# CC2538_Flashing_-_FTDI.net
KiCad netlist of a schematic drawn in Altium Designer
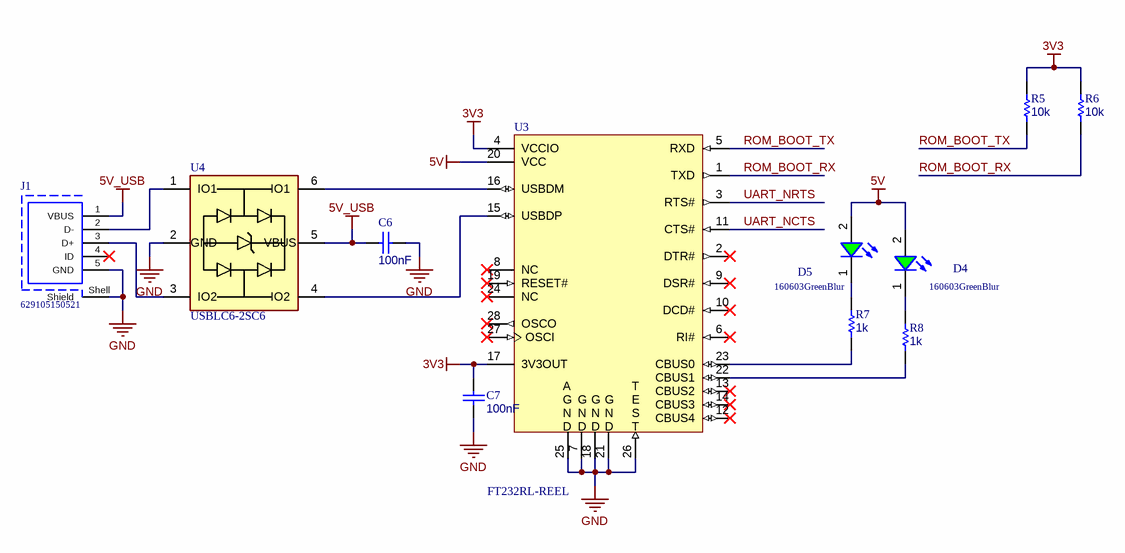
[diagram p0: [CC2538] Flashing - FTDI.SchDoc]

(export (version "E")
  (design (tool "Eeschema 10.0.6"))
  (components
    (comp (ref "C6")
      (value "100nF")
      (footprint "CAP_0603")
      (description "CAP, size 0603, 100 nF, 50 VDC, 10%")
      (fields
        (field (name "MANUFACTURER PART NUMBER") "CGA3E3X8R1H104K080AE")
        (field (name "LCSC PART #") "C14663")
        (field (name "SOURCE") "Capacitor_0603_10_percent.SchLib")
      )
      (libsource (lib "University of Technology") (part "010603475106.3"))
    )
    (comp (ref "C7")
      (value "100nF")
      (footprint "CAP_0603")
      (description "CAP, size 0603, 100 nF, 50 VDC, 10%")
      (fields
        (field (name "MANUFACTURER PART NUMBER") "CGA3E3X8R1H104K080AE")
        (field (name "LCSC PART #") "C14663")
        (field (name "SOURCE") "Capacitor_0603_10_percent.SchLib")
      )
      (libsource (lib "University of Technology") (part "010603475106.3"))
    )
    (comp (ref "D4")
      (value "160603GreenBlur")
      (footprint "WL-SMCW_0603_H=0.7mm")
      (description "WL-SMCW SMT Mono-color Chip LED Blur, size 0603, Green, 3.2V, 140deg")
      (libsource (lib "University of Technology") (part "160603GreenClear"))
    )
    (comp (ref "D5")
      (value "160603GreenBlur")
      (footprint "WL-SMCW_0603_H=0.7mm")
      (description "WL-SMCW SMT Mono-color Chip LED Blur, size 0603, Green, 3.2V, 140deg")
      (libsource (lib "University of Technology") (part "160603GreenClear"))
    )
    (comp (ref "J1")
      (value "629105150521")
      (footprint "629105150521")
      (description "Micro USB 2.0 Type B Receptacle WR-COM, Horizontal, SMT, with Pegs, High Current at Pin 1 & Pin 5")
      (libsource (lib "University of Technology") (part "Micro USB 2.0"))
    )
    (comp (ref "R5")
      (value "10k")
      (footprint "RES_0603")
      (description "RES, size 0603, 10 KOhm, 1/10 W, 1%")
      (fields
        (field (name "MANUFACTURER PART NUMBER") "RC0603FR-0710KL")
        (field (name "MANUFACTURER") "YAGEO")
      )
      (libsource (lib "University of Technology") (part "00060371541"))
    )
    (comp (ref "R6")
      (value "10k")
      (footprint "RES_0603")
      (description "RES, size 0603, 10 KOhm, 1/10 W, 1%")
      (fields
        (field (name "MANUFACTURER PART NUMBER") "RC0603FR-0710KL")
        (field (name "MANUFACTURER") "YAGEO")
      )
      (libsource (lib "University of Technology") (part "00060371541"))
    )
    (comp (ref "R7")
      (value "1k")
      (footprint "RES_0603")
      (description "RES, size 0603, 1 KOhm, 1/10 W, 1%")
      (fields (field (name "TOLERANCE") "1%") (field (name "MANUFACTURER PART NUMBER") "RC0603FR-071KL"))
      (libsource (lib "University of Technology") (part "00060371541"))
    )
    (comp (ref "R8")
      (value "1k")
      (footprint "RES_0603")
      (description "RES, size 0603, 1 KOhm, 1/10 W, 1%")
      (fields (field (name "TOLERANCE") "1%") (field (name "MANUFACTURER PART NUMBER") "RC0603FR-071KL"))
      (libsource (lib "University of Technology") (part "00060371541"))
    )
    (comp (ref "U3")
      (value "FT232RL-REEL")
      (footprint "FTDI-SSOP-28_L")
      (description "USB UART IC, -0.5 to 6 V, 24 mA, -40 to 85 degC, 28-Pin SSOP, RoHS, Tape and Reel")
      (fields (field (name "MANUFACTURER") "Future Technology Devices International (FTDI)"))
      (libsource (lib "University of Technology") (part "FTDI-FT232-SSOP-28"))
    )
    (comp (ref "U4")
      (value "USBLC6-2SC6")
      (footprint "USBLC6-2SC6-Footprint-1")
      (description "17V Clamp 5A (8/20Âµs) Ipp Tvs Diode Surface Mount SOT-23-6")
      (libsource (lib "University of Technology") (part "USBLC6"))
    )
  )
  (nets
    (net (code "1") (name "/ROM_BOOT_RX") (class "Default")
      (node (ref "R6") (pin "1") (pinfunction "1_1") (pintype "passive"))
      (node (ref "U3") (pin "1") (pinfunction "TXD_1") (pintype "output"))
    )
    (net (code "2") (name "/ROM_BOOT_TX") (class "Default")
      (node (ref "R5") (pin "1") (pinfunction "1_1") (pintype "passive"))
      (node (ref "U3") (pin "5") (pinfunction "RXD_5") (pintype "input"))
    )
    (net (code "3") (name "/UART_NCTS") (class "Default")
      (node (ref "U3") (pin "11") (pinfunction "CTS#_11") (pintype "input"))
    )
    (net (code "4") (name "/UART_NRTS") (class "Default")
      (node (ref "U3") (pin "3") (pinfunction "RTS#_3") (pintype "output"))
    )
    (net (code "5") (name "3V3") (class "Default")
      (node (ref "C7") (pin "2") (pinfunction "2_2") (pintype "passive"))
      (node (ref "R5") (pin "2") (pinfunction "2_2") (pintype "passive"))
      (node (ref "R6") (pin "2") (pinfunction "2_2") (pintype "passive"))
      (node (ref "U3") (pin "17") (pinfunction "3V3OUT_17") (pintype "power_in"))
      (node (ref "U3") (pin "4") (pinfunction "VCCIO_4") (pintype "power_in"))
    )
    (net (code "6") (name "5V") (class "Default")
      (node (ref "D4") (pin "2") (pinfunction "A_2") (pintype "passive"))
      (node (ref "D5") (pin "2") (pinfunction "A_2") (pintype "passive"))
      (node (ref "U3") (pin "20") (pinfunction "VCC_20") (pintype "power_in"))
    )
    (net (code "7") (name "5V_USB") (class "Default")
      (node (ref "C6") (pin "2") (pinfunction "2_2") (pintype "passive"))
      (node (ref "J1") (pin "1") (pinfunction "VBUS_1") (pintype "passive"))
      (node (ref "U4") (pin "5") (pinfunction "VBUS_5") (pintype "power_in"))
    )
    (net (code "8") (name "GND") (class "Default")
      (node (ref "C6") (pin "1") (pinfunction "1_1") (pintype "passive"))
      (node (ref "C7") (pin "1") (pinfunction "1_1") (pintype "passive"))
      (node (ref "J1") (pin "5") (pinfunction "GND_5") (pintype "passive"))
      (node (ref "J1") (pin "Shell") (pinfunction "Shield_Shell") (pintype "passive"))
      (node (ref "U3") (pin "18") (pinfunction "GND_18") (pintype "power_in"))
      (node (ref "U3") (pin "21") (pinfunction "GND_21") (pintype "power_in"))
      (node (ref "U3") (pin "25") (pinfunction "AGND_25") (pintype "power_in"))
      (node (ref "U3") (pin "26") (pinfunction "TEST_26") (pintype "input"))
      (node (ref "U3") (pin "7") (pinfunction "GND_7") (pintype "power_in"))
      (node (ref "U4") (pin "2") (pinfunction "GND_2") (pintype "power_in"))
    )
    (net (code "9") (name "Net-(D4-K)") (class "Default")
      (node (ref "D4") (pin "1") (pinfunction "K_1") (pintype "passive"))
      (node (ref "R8") (pin "2") (pinfunction "2_2") (pintype "passive"))
    )
    (net (code "10") (name "Net-(D5-K)") (class "Default")
      (node (ref "D5") (pin "1") (pinfunction "K_1") (pintype "passive"))
      (node (ref "R7") (pin "2") (pinfunction "2_2") (pintype "passive"))
    )
    (net (code "11") (name "Net-(J1-D+)") (class "Default")
      (node (ref "J1") (pin "3") (pinfunction "D+_3") (pintype "passive"))
      (node (ref "U4") (pin "3") (pinfunction "IO2_3") (pintype "passive"))
    )
    (net (code "12") (name "Net-(J1-D-)") (class "Default")
      (node (ref "J1") (pin "2") (pinfunction "D-_2") (pintype "passive"))
      (node (ref "U4") (pin "1") (pinfunction "IO1_1") (pintype "passive"))
    )
    (net (code "13") (name "Net-(U3-CBUS0)") (class "Default")
      (node (ref "R7") (pin "1") (pinfunction "1_1") (pintype "passive"))
      (node (ref "U3") (pin "23") (pinfunction "CBUS0_23") (pintype "bidirectional"))
    )
    (net (code "14") (name "Net-(U3-CBUS1)") (class "Default")
      (node (ref "R8") (pin "1") (pinfunction "1_1") (pintype "passive"))
      (node (ref "U3") (pin "22") (pinfunction "CBUS1_22") (pintype "bidirectional"))
    )
    (net (code "15") (name "Net-(U3-USBDM)") (class "Default")
      (node (ref "U3") (pin "16") (pinfunction "USBDM_16") (pintype "bidirectional"))
      (node (ref "U4") (pin "6") (pinfunction "IO1_6") (pintype "passive"))
    )
    (net (code "16") (name "Net-(U3-USBDP)") (class "Default")
      (node (ref "U3") (pin "15") (pinfunction "USBDP_15") (pintype "bidirectional"))
      (node (ref "U4") (pin "4") (pinfunction "IO2_4") (pintype "passive"))
    )
    (net (code "17") (name "unconnected-(J1-ID-Pad4)") (class "Default")
      (node (ref "J1") (pin "4") (pinfunction "ID_4") (pintype "passive+no_connect"))
    )
    (net (code "18") (name "unconnected-(U3-CBUS2-Pad13)") (class "Default")
      (node (ref "U3") (pin "13") (pinfunction "CBUS2_13") (pintype "bidirectional+no_connect"))
    )
    (net (code "19") (name "unconnected-(U3-CBUS3-Pad14)") (class "Default")
      (node (ref "U3") (pin "14") (pinfunction "CBUS3_14") (pintype "bidirectional+no_connect"))
    )
    (net (code "20") (name "unconnected-(U3-CBUS4-Pad12)") (class "Default")
      (node (ref "U3") (pin "12") (pinfunction "CBUS4_12") (pintype "bidirectional+no_connect"))
    )
    (net (code "21") (name "unconnected-(U3-DCD#-Pad10)") (class "Default")
      (node (ref "U3") (pin "10") (pinfunction "DCD#_10") (pintype "input+no_connect"))
    )
    (net (code "22") (name "unconnected-(U3-DSR#-Pad9)") (class "Default")
      (node (ref "U3") (pin "9") (pinfunction "DSR#_9") (pintype "input+no_connect"))
    )
    (net (code "23") (name "unconnected-(U3-DTR#-Pad2)") (class "Default")
      (node (ref "U3") (pin "2") (pinfunction "DTR#_2") (pintype "output+no_connect"))
    )
    (net (code "24") (name "unconnected-(U3-NC-Pad8)") (class "Default")
      (node (ref "U3") (pin "8") (pinfunction "NC_8") (pintype "passive+no_connect"))
    )
    (net (code "25") (name "unconnected-(U3-NC-Pad24)") (class "Default")
      (node (ref "U3") (pin "24") (pinfunction "NC_24") (pintype "passive+no_connect"))
    )
    (net (code "26") (name "unconnected-(U3-OSCI-Pad27)") (class "Default")
      (node (ref "U3") (pin "27") (pinfunction "OSCI_27") (pintype "input+no_connect"))
    )
    (net (code "27") (name "unconnected-(U3-OSCO-Pad28)") (class "Default")
      (node (ref "U3") (pin "28") (pinfunction "OSCO_28") (pintype "output+no_connect"))
    )
    (net (code "28") (name "unconnected-(U3-RESET#-Pad19)") (class "Default")
      (node (ref "U3") (pin "19") (pinfunction "RESET#_19") (pintype "input+no_connect"))
    )
    (net (code "29") (name "unconnected-(U3-RI#-Pad6)") (class "Default")
      (node (ref "U3") (pin "6") (pinfunction "RI#_6") (pintype "input+no_connect"))
    )
  )
)
